# Sheet_UL.net
KiCad netlist of a schematic drawn in Altium Designer
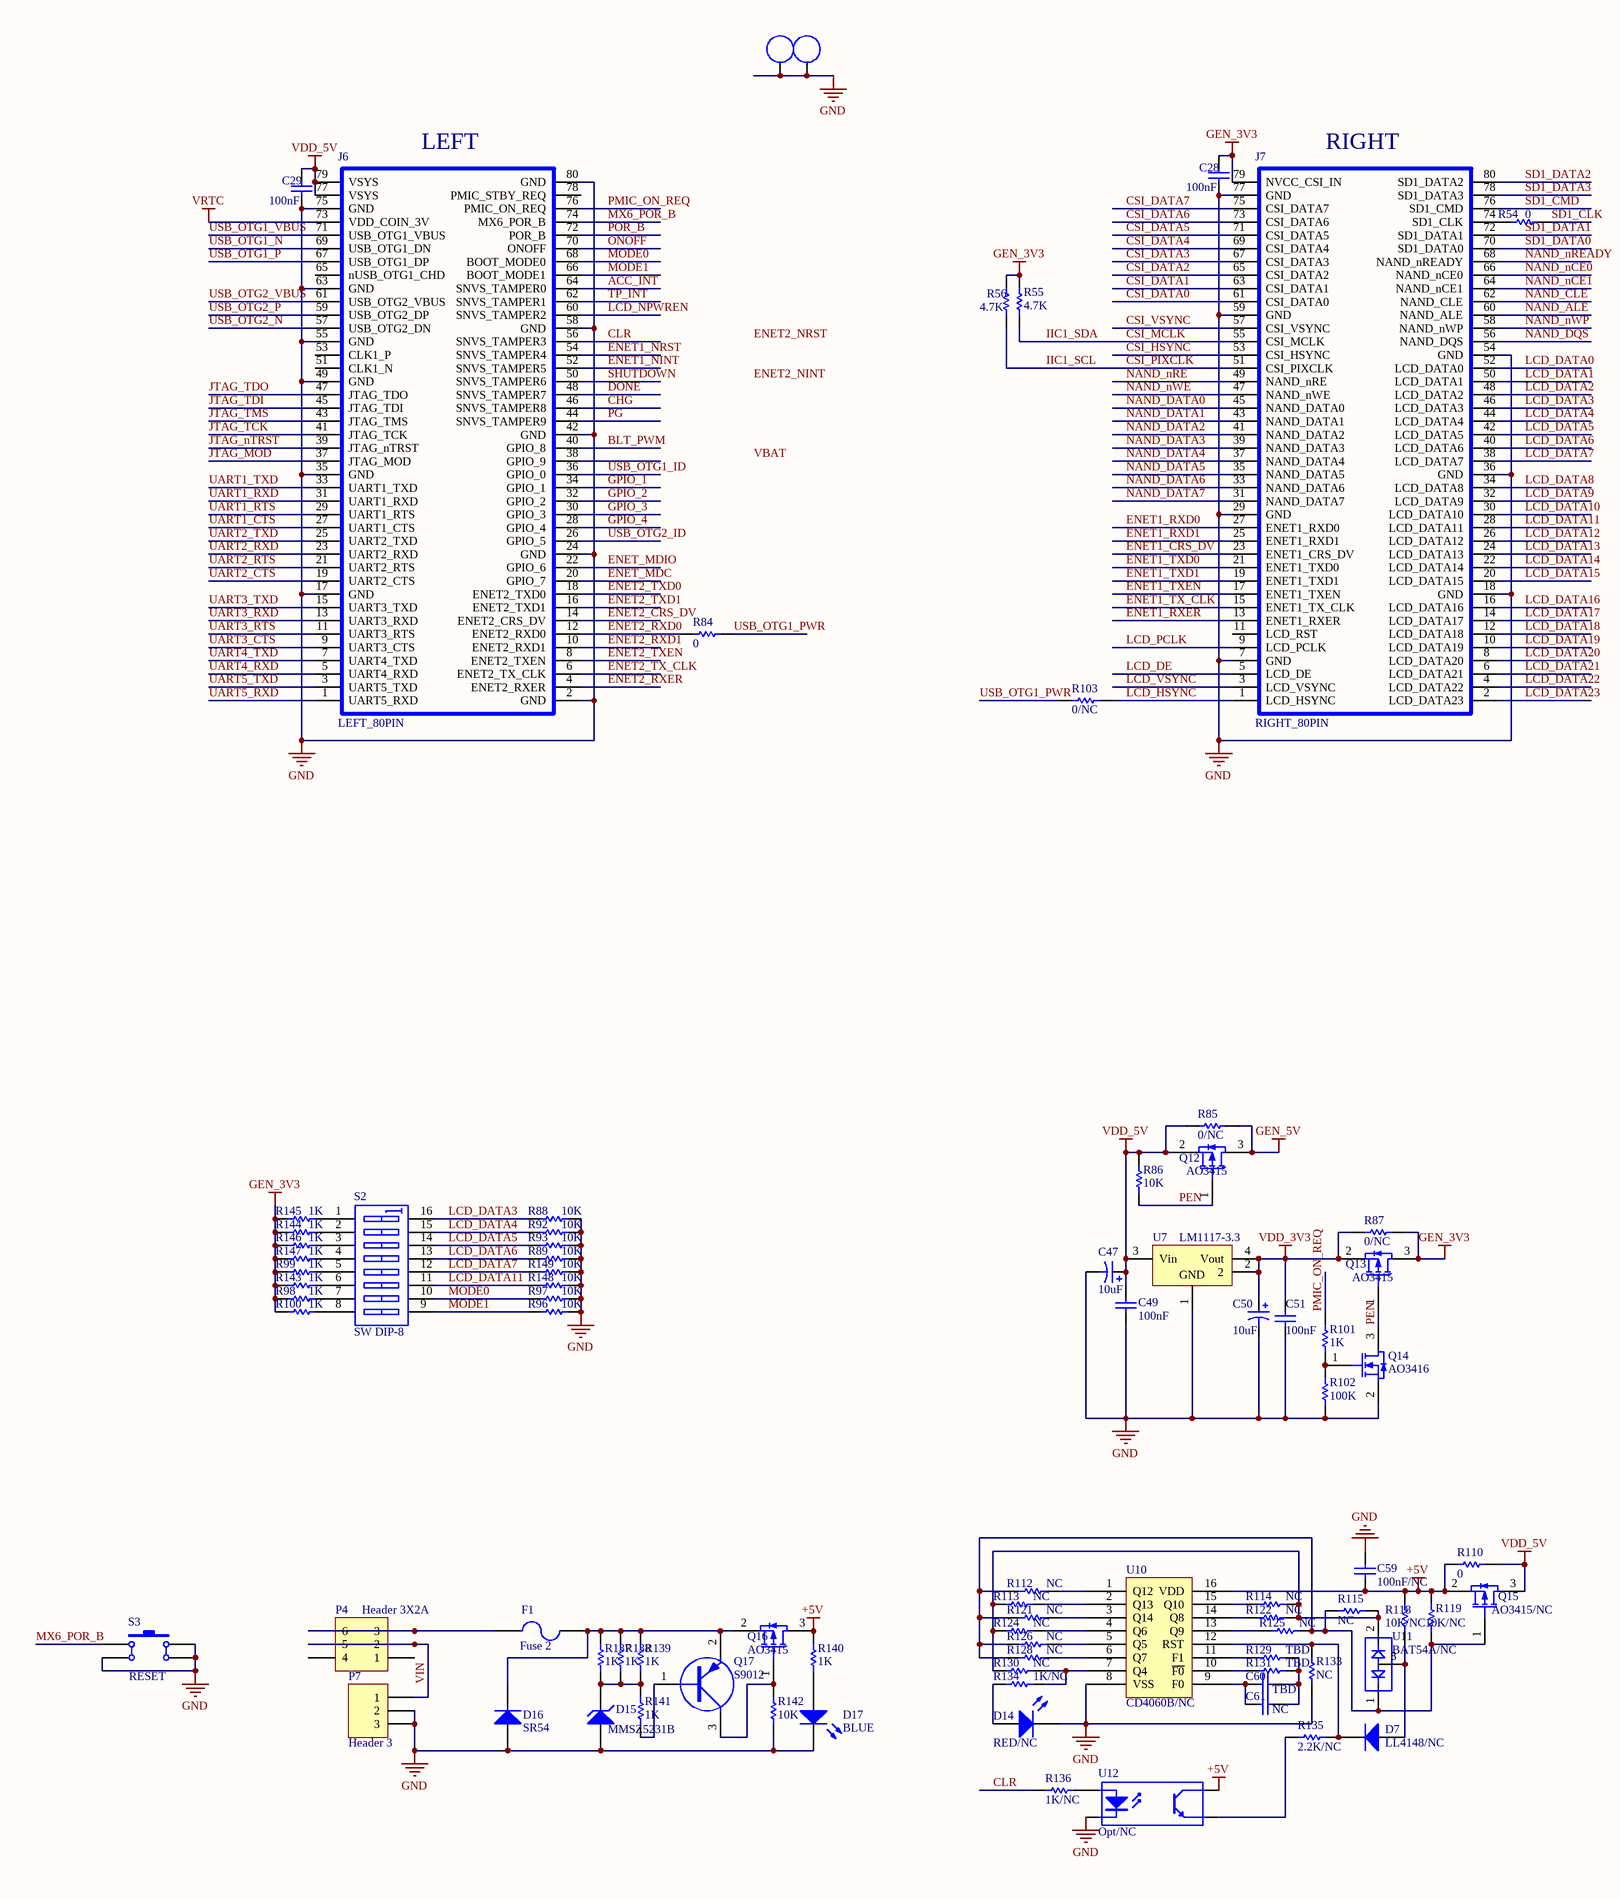
[diagram p0: Sheet_UL.SchDoc, left]
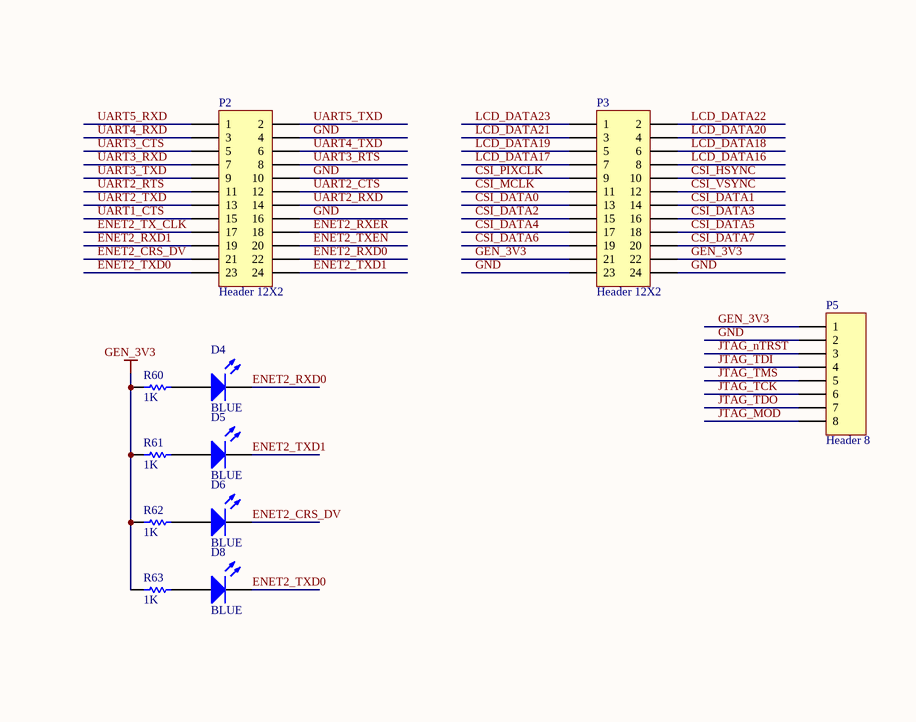
[diagram p1: Sheet_UL.SchDoc, right]

(export (version "E")
  (design (tool "Eeschema 10.0.6"))
  (components
    (comp (ref "C28")
      (value "100nF")
      (footprint "0603")
      (description "Capacitor")
      (fields (field (name "Comment") "Cap") (field (name "PUBLISHER") "Altium Limited"))
      (libsource (lib "Miscellaneous Devices") (part "Cap"))
    )
    (comp (ref "C29")
      (value "100nF")
      (footprint "0603")
      (description "Capacitor")
      (fields (field (name "Comment") "Cap") (field (name "PUBLISHER") "Altium Limited"))
      (libsource (lib "Miscellaneous Devices") (part "Cap"))
    )
    (comp (ref "C47")
      (value "10uF")
      (footprint "3216A")
      (description "Polarized Capacitor (Radial)")
      (fields (field (name "Comment") "Cap Pol1") (field (name "PUBLISHER") "Altium Limited"))
      (libsource (lib "Miscellaneous Devices") (part "Cap Pol1"))
    )
    (comp (ref "C49")
      (value "100nF")
      (footprint "0603")
      (description "Capacitor")
      (fields (field (name "Comment") "Cap") (field (name "PUBLISHER") "Altium Limited"))
      (libsource (lib "Miscellaneous Devices") (part "Cap"))
    )
    (comp (ref "C50")
      (value "10uF")
      (footprint "3216A")
      (description "Polarized Capacitor (Radial)")
      (fields (field (name "Comment") "Cap Pol1") (field (name "PUBLISHER") "Altium Limited"))
      (libsource (lib "Miscellaneous Devices") (part "Cap Pol1"))
    )
    (comp (ref "C51")
      (value "100nF")
      (footprint "0603")
      (description "Capacitor")
      (fields (field (name "Comment") "Cap") (field (name "PUBLISHER") "Altium Limited"))
      (libsource (lib "Miscellaneous Devices") (part "Cap"))
    )
    (comp (ref "C59")
      (value "100nF/NC")
      (footprint "0603")
      (description "Capacitor")
      (fields (field (name "Comment") "Cap") (field (name "PUBLISHER") "Altium Limited"))
      (libsource (lib "Miscellaneous Devices") (part "Cap"))
    )
    (comp (ref "C60")
      (value "TBD")
      (footprint "0603")
      (description "Capacitor")
      (fields (field (name "Comment") "Cap") (field (name "PUBLISHER") "Altium Limited"))
      (libsource (lib "Miscellaneous Devices") (part "Cap"))
    )
    (comp (ref "C61")
      (value "NC")
      (footprint "0603")
      (description "Capacitor")
      (fields (field (name "Comment") "Cap") (field (name "PUBLISHER") "Altium Limited"))
      (libsource (lib "Miscellaneous Devices") (part "Cap"))
    )
    (comp (ref "D4")
      (value "BLUE")
      (footprint "0603_")
      (description "Typical INFRARED GaAs LED")
      (fields (field (name "PUBLISHER") "Altium Limited"))
      (libsource (lib "Miscellaneous Devices") (part "LED0"))
    )
    (comp (ref "D5")
      (value "BLUE")
      (footprint "0603_")
      (description "Typical INFRARED GaAs LED")
      (fields (field (name "PUBLISHER") "Altium Limited"))
      (libsource (lib "Miscellaneous Devices") (part "LED0"))
    )
    (comp (ref "D6")
      (value "BLUE")
      (footprint "0603_")
      (description "Typical INFRARED GaAs LED")
      (fields (field (name "PUBLISHER") "Altium Limited"))
      (libsource (lib "Miscellaneous Devices") (part "LED0"))
    )
    (comp (ref "D7")
      (value "LL4148/NC")
      (footprint "1206_")
      (description "Default Diode")
      (fields (field (name "PUBLISHER") "Altium Limited"))
      (libsource (lib "Miscellaneous Devices") (part "Diode"))
    )
    (comp (ref "D8")
      (value "BLUE")
      (footprint "0603_")
      (description "Typical INFRARED GaAs LED")
      (fields (field (name "PUBLISHER") "Altium Limited"))
      (libsource (lib "Miscellaneous Devices") (part "LED0"))
    )
    (comp (ref "D14")
      (value "RED/NC")
      (footprint "0603_")
      (description "Typical INFRARED GaAs LED")
      (fields (field (name "PUBLISHER") "Altium Limited"))
      (libsource (lib "Miscellaneous Devices") (part "LED0"))
    )
    (comp (ref "D15")
      (value "MMSZ5231B")
      (footprint "SOD-123")
      (description "Zener Diode")
      (fields (field (name "PUBLISHER") "Altium Limited"))
      (libsource (lib "Miscellaneous Devices") (part "D Zener"))
    )
    (comp (ref "D16")
      (value "SR54")
      (footprint "SMB/DO-214AA")
      (description "Default Diode")
      (fields (field (name "PUBLISHER") "Altium Limited"))
      (libsource (lib "Miscellaneous Devices") (part "Diode"))
    )
    (comp (ref "D17")
      (value "BLUE")
      (footprint "0603_")
      (description "Typical INFRARED GaAs LED")
      (fields (field (name "PUBLISHER") "Altium Limited"))
      (libsource (lib "Miscellaneous Devices") (part "LED0"))
    )
    (comp (ref "F1")
      (value "Fuse 2")
      (footprint "1812")
      (description "Fuse")
      (fields (field (name "PUBLISHER") "Altium Limited"))
      (libsource (lib "Miscellaneous Devices") (part "Fuse 2"))
    )
    (comp (ref "H10") (value "hole") (footprint "HOLE_2") (libsource (lib "arm_SL") (part "hole")))
    (comp (ref "H11") (value "hole") (footprint "HOLE_2") (libsource (lib "arm_SL") (part "hole")))
    (comp (ref "J6")
      (value "LEFT_80PIN")
      (footprint "CON_80")
      (libsource (lib "Schlib_UL") (part "LEFT_80PIN"))
    )
    (comp (ref "J7")
      (value "RIGHT_80PIN")
      (footprint "CON_80")
      (libsource (lib "Schlib_UL") (part "RIGHT_80PIN"))
    )
    (comp (ref "P2")
      (value "Header 12X2")
      (footprint "HDR2X12")
      (description "Header, 12-Pin, Dual row")
      (fields (field (name "PUBLISHER") "Altium Limited"))
      (libsource (lib "Miscellaneous Connectors") (part "Header 12X2"))
    )
    (comp (ref "P3")
      (value "Header 12X2")
      (footprint "HDR2X12")
      (description "Header, 12-Pin, Dual row")
      (fields (field (name "PUBLISHER") "Altium Limited"))
      (libsource (lib "Miscellaneous Connectors") (part "Header 12X2"))
    )
    (comp (ref "P4")
      (value "Header 3X2A")
      (footprint "ZSKG_8.5_8.5")
      (description "Header, 3-Pin, Dual row")
      (fields (field (name "PUBLISHER") "Altium Limited"))
      (libsource (lib "Miscellaneous Connectors") (part "Header 3X2A"))
    )
    (comp (ref "P5")
      (value "Header 8")
      (footprint "HDR1X8")
      (description "Header, 8-Pin")
      (fields (field (name "PUBLISHER") "Altium Limited"))
      (libsource (lib "Miscellaneous Connectors") (part "Header 8"))
    )
    (comp (ref "P7")
      (value "Header 3")
      (footprint "JACK-2.5MM_B")
      (description "Header, 3-Pin")
      (fields (field (name "PUBLISHER") "Altium Limited"))
      (libsource (lib "Miscellaneous Connectors") (part "Header 3"))
    )
    (comp (ref "Q12")
      (value "AO3415")
      (footprint "SOT23")
      (description "P-Channel MOSFET")
      (fields (field (name "PUBLISHER") "Altium Limited"))
      (libsource (lib "Schlib1") (part "MOSFET-P_1"))
    )
    (comp (ref "Q13")
      (value "AO3415")
      (footprint "SOT23")
      (description "P-Channel MOSFET")
      (fields (field (name "PUBLISHER") "Altium Limited"))
      (libsource (lib "Schlib1") (part "MOSFET-P_1"))
    )
    (comp (ref "Q14")
      (value "AO3416")
      (footprint "SOT23")
      (description "N-Channel MOSFET")
      (fields (field (name "PUBLISHER") "Altium Limited"))
      (libsource (lib "Schlib_UL") (part "MOSFET-P_1"))
    )
    (comp (ref "Q15")
      (value "AO3415/NC")
      (footprint "SOT23")
      (description "P-Channel MOSFET")
      (fields (field (name "PUBLISHER") "Altium Limited"))
      (libsource (lib "Schlib1") (part "MOSFET-P_1"))
    )
    (comp (ref "Q16")
      (value "AO3415")
      (footprint "SOT23")
      (description "P-Channel MOSFET")
      (fields (field (name "PUBLISHER") "Altium Limited"))
      (libsource (lib "Schlib1") (part "MOSFET-P_1"))
    )
    (comp (ref "Q17")
      (value "S9012")
      (footprint "SOT23")
      (description "PNP Transistor")
      (libsource (lib "Schlib_YX") (part "PNP"))
    )
    (comp (ref "R54")
      (value "0")
      (footprint "0603")
      (description "Resistor")
      (fields (field (name "Comment") "Res1") (field (name "PUBLISHER") "Altium Limited"))
      (libsource (lib "Miscellaneous Devices") (part "Res1"))
    )
    (comp (ref "R55")
      (value "4.7K")
      (footprint "0603")
      (description "Resistor")
      (fields (field (name "Comment") "Res1") (field (name "PUBLISHER") "Altium Limited"))
      (libsource (lib "Miscellaneous Devices") (part "Res1"))
    )
    (comp (ref "R56")
      (value "4.7K")
      (footprint "0603")
      (description "Resistor")
      (fields (field (name "Comment") "Res1") (field (name "PUBLISHER") "Altium Limited"))
      (libsource (lib "Miscellaneous Devices") (part "Res1"))
    )
    (comp (ref "R60")
      (value "1K")
      (footprint "0603")
      (description "Resistor")
      (fields (field (name "Comment") "Res1") (field (name "PUBLISHER") "Altium Limited"))
      (libsource (lib "Miscellaneous Devices") (part "Res1"))
    )
    (comp (ref "R61")
      (value "1K")
      (footprint "0603")
      (description "Resistor")
      (fields (field (name "Comment") "Res1") (field (name "PUBLISHER") "Altium Limited"))
      (libsource (lib "Miscellaneous Devices") (part "Res1"))
    )
    (comp (ref "R62")
      (value "1K")
      (footprint "0603")
      (description "Resistor")
      (fields (field (name "Comment") "Res1") (field (name "PUBLISHER") "Altium Limited"))
      (libsource (lib "Miscellaneous Devices") (part "Res1"))
    )
    (comp (ref "R63")
      (value "1K")
      (footprint "0603")
      (description "Resistor")
      (fields (field (name "Comment") "Res1") (field (name "PUBLISHER") "Altium Limited"))
      (libsource (lib "Miscellaneous Devices") (part "Res1"))
    )
    (comp (ref "R84")
      (value "0")
      (footprint "0603")
      (description "Resistor")
      (fields (field (name "Comment") "Res1") (field (name "PUBLISHER") "Altium Limited"))
      (libsource (lib "Miscellaneous Devices") (part "Res1"))
    )
    (comp (ref "R85")
      (value "0/NC")
      (footprint "0805")
      (description "Resistor")
      (fields (field (name "Comment") "Res1") (field (name "PUBLISHER") "Altium Limited"))
      (libsource (lib "Miscellaneous Devices") (part "Res1"))
    )
    (comp (ref "R86")
      (value "10K")
      (footprint "0603")
      (description "Resistor")
      (fields (field (name "Comment") "Res1") (field (name "PUBLISHER") "Altium Limited"))
      (libsource (lib "Miscellaneous Devices") (part "Res1"))
    )
    (comp (ref "R87")
      (value "0/NC")
      (footprint "0603")
      (description "Resistor")
      (fields (field (name "Comment") "Res1") (field (name "PUBLISHER") "Altium Limited"))
      (libsource (lib "Miscellaneous Devices") (part "Res1"))
    )
    (comp (ref "R88")
      (value "10K")
      (footprint "0603")
      (description "Resistor")
      (fields (field (name "Comment") "Res1") (field (name "PUBLISHER") "Altium Limited"))
      (libsource (lib "Miscellaneous Devices") (part "Res1"))
    )
    (comp (ref "R89")
      (value "10K")
      (footprint "0603")
      (description "Resistor")
      (fields (field (name "Comment") "Res1") (field (name "PUBLISHER") "Altium Limited"))
      (libsource (lib "Miscellaneous Devices") (part "Res1"))
    )
    (comp (ref "R92")
      (value "10K")
      (footprint "0603")
      (description "Resistor")
      (fields (field (name "Comment") "Res1") (field (name "PUBLISHER") "Altium Limited"))
      (libsource (lib "Miscellaneous Devices") (part "Res1"))
    )
    (comp (ref "R93")
      (value "10K")
      (footprint "0603")
      (description "Resistor")
      (fields (field (name "Comment") "Res1") (field (name "PUBLISHER") "Altium Limited"))
      (libsource (lib "Miscellaneous Devices") (part "Res1"))
    )
    (comp (ref "R96")
      (value "10K")
      (footprint "0603")
      (description "Resistor")
      (fields (field (name "Comment") "Res1") (field (name "PUBLISHER") "Altium Limited"))
      (libsource (lib "Miscellaneous Devices") (part "Res1"))
    )
    (comp (ref "R97")
      (value "10K")
      (footprint "0603")
      (description "Resistor")
      (fields (field (name "Comment") "Res1") (field (name "PUBLISHER") "Altium Limited"))
      (libsource (lib "Miscellaneous Devices") (part "Res1"))
    )
    (comp (ref "R98")
      (value "1K")
      (footprint "0603")
      (description "Resistor")
      (fields (field (name "Comment") "Res1") (field (name "PUBLISHER") "Altium Limited"))
      (libsource (lib "Miscellaneous Devices") (part "Res1"))
    )
    (comp (ref "R99")
      (value "1K")
      (footprint "0603")
      (description "Resistor")
      (fields (field (name "Comment") "Res1") (field (name "PUBLISHER") "Altium Limited"))
      (libsource (lib "Miscellaneous Devices") (part "Res1"))
    )
    (comp (ref "R100")
      (value "1K")
      (footprint "0603")
      (description "Resistor")
      (fields (field (name "Comment") "Res1") (field (name "PUBLISHER") "Altium Limited"))
      (libsource (lib "Miscellaneous Devices") (part "Res1"))
    )
    (comp (ref "R101")
      (value "1K")
      (footprint "0603")
      (description "Resistor")
      (fields (field (name "Comment") "Res1") (field (name "PUBLISHER") "Altium Limited"))
      (libsource (lib "Miscellaneous Devices") (part "Res1"))
    )
    (comp (ref "R102")
      (value "100K")
      (footprint "0603")
      (description "Resistor")
      (fields (field (name "Comment") "Res1") (field (name "PUBLISHER") "Altium Limited"))
      (libsource (lib "Miscellaneous Devices") (part "Res1"))
    )
    (comp (ref "R103")
      (value "0/NC")
      (footprint "0603")
      (description "Resistor")
      (fields (field (name "Comment") "Res1") (field (name "PUBLISHER") "Altium Limited"))
      (libsource (lib "Miscellaneous Devices") (part "Res1"))
    )
    (comp (ref "R110")
      (value "0")
      (footprint "0805")
      (description "Resistor")
      (fields (field (name "Comment") "Res1") (field (name "PUBLISHER") "Altium Limited"))
      (libsource (lib "Miscellaneous Devices") (part "Res1"))
    )
    (comp (ref "R112")
      (value "NC")
      (footprint "0603")
      (description "Resistor")
      (fields (field (name "Comment") "Res1") (field (name "PUBLISHER") "Altium Limited"))
      (libsource (lib "Miscellaneous Devices") (part "Res1"))
    )
    (comp (ref "R113")
      (value "NC")
      (footprint "0603")
      (description "Resistor")
      (fields (field (name "Comment") "Res1") (field (name "PUBLISHER") "Altium Limited"))
      (libsource (lib "Miscellaneous Devices") (part "Res1"))
    )
    (comp (ref "R114")
      (value "NC")
      (footprint "0603")
      (description "Resistor")
      (fields (field (name "Comment") "Res1") (field (name "PUBLISHER") "Altium Limited"))
      (libsource (lib "Miscellaneous Devices") (part "Res1"))
    )
    (comp (ref "R115")
      (value "NC")
      (footprint "0603")
      (description "Resistor")
      (fields (field (name "Comment") "Res1") (field (name "PUBLISHER") "Altium Limited"))
      (libsource (lib "Miscellaneous Devices") (part "Res1"))
    )
    (comp (ref "R118")
      (value "10K/NC")
      (footprint "0603")
      (description "Resistor")
      (fields (field (name "Comment") "Res1") (field (name "PUBLISHER") "Altium Limited"))
      (libsource (lib "Miscellaneous Devices") (part "Res1"))
    )
    (comp (ref "R119")
      (value "10K/NC")
      (footprint "0603")
      (description "Resistor")
      (fields (field (name "Comment") "Res1") (field (name "PUBLISHER") "Altium Limited"))
      (libsource (lib "Miscellaneous Devices") (part "Res1"))
    )
    (comp (ref "R121")
      (value "NC")
      (footprint "0603")
      (description "Resistor")
      (fields (field (name "Comment") "Res1") (field (name "PUBLISHER") "Altium Limited"))
      (libsource (lib "Miscellaneous Devices") (part "Res1"))
    )
    (comp (ref "R122")
      (value "NC")
      (footprint "0603")
      (description "Resistor")
      (fields (field (name "Comment") "Res1") (field (name "PUBLISHER") "Altium Limited"))
      (libsource (lib "Miscellaneous Devices") (part "Res1"))
    )
    (comp (ref "R124")
      (value "NC")
      (footprint "0603")
      (description "Resistor")
      (fields (field (name "Comment") "Res1") (field (name "PUBLISHER") "Altium Limited"))
      (libsource (lib "Miscellaneous Devices") (part "Res1"))
    )
    (comp (ref "R125")
      (value "NC")
      (footprint "0603")
      (description "Resistor")
      (fields (field (name "Comment") "Res1") (field (name "PUBLISHER") "Altium Limited"))
      (libsource (lib "Miscellaneous Devices") (part "Res1"))
    )
    (comp (ref "R126")
      (value "NC")
      (footprint "0603")
      (description "Resistor")
      (fields (field (name "Comment") "Res1") (field (name "PUBLISHER") "Altium Limited"))
      (libsource (lib "Miscellaneous Devices") (part "Res1"))
    )
    (comp (ref "R128")
      (value "NC")
      (footprint "0603")
      (description "Resistor")
      (fields (field (name "Comment") "Res1") (field (name "PUBLISHER") "Altium Limited"))
      (libsource (lib "Miscellaneous Devices") (part "Res1"))
    )
    (comp (ref "R129")
      (value "TBD")
      (footprint "0603")
      (description "Resistor")
      (fields (field (name "Comment") "Res1") (field (name "PUBLISHER") "Altium Limited"))
      (libsource (lib "Miscellaneous Devices") (part "Res1"))
    )
    (comp (ref "R130")
      (value "NC")
      (footprint "0603")
      (description "Resistor")
      (fields (field (name "Comment") "Res1") (field (name "PUBLISHER") "Altium Limited"))
      (libsource (lib "Miscellaneous Devices") (part "Res1"))
    )
    (comp (ref "R131")
      (value "TBD")
      (footprint "0603")
      (description "Resistor")
      (fields (field (name "Comment") "Res1") (field (name "PUBLISHER") "Altium Limited"))
      (libsource (lib "Miscellaneous Devices") (part "Res1"))
    )
    (comp (ref "R133")
      (value "NC")
      (footprint "0603")
      (description "Resistor")
      (fields (field (name "Comment") "Res1") (field (name "PUBLISHER") "Altium Limited"))
      (libsource (lib "Miscellaneous Devices") (part "Res1"))
    )
    (comp (ref "R134")
      (value "1K/NC")
      (footprint "0603")
      (description "Resistor")
      (fields (field (name "Comment") "Res1") (field (name "PUBLISHER") "Altium Limited"))
      (libsource (lib "Miscellaneous Devices") (part "Res1"))
    )
    (comp (ref "R135")
      (value "2.2K/NC")
      (footprint "0603")
      (description "Resistor")
      (fields (field (name "Comment") "Res1") (field (name "PUBLISHER") "Altium Limited"))
      (libsource (lib "Miscellaneous Devices") (part "Res1"))
    )
    (comp (ref "R136")
      (value "1K/NC")
      (footprint "0603")
      (description "Resistor")
      (fields (field (name "Comment") "Res1") (field (name "PUBLISHER") "Altium Limited"))
      (libsource (lib "Miscellaneous Devices") (part "Res1"))
    )
    (comp (ref "R137")
      (value "1K")
      (footprint "0603")
      (description "Resistor")
      (fields (field (name "Comment") "Res1") (field (name "PUBLISHER") "Altium Limited"))
      (libsource (lib "Miscellaneous Devices") (part "Res1"))
    )
    (comp (ref "R138")
      (value "1K")
      (footprint "0603")
      (description "Resistor")
      (fields (field (name "Comment") "Res1") (field (name "PUBLISHER") "Altium Limited"))
      (libsource (lib "Miscellaneous Devices") (part "Res1"))
    )
    (comp (ref "R139")
      (value "1K")
      (footprint "0603")
      (description "Resistor")
      (fields (field (name "Comment") "Res1") (field (name "PUBLISHER") "Altium Limited"))
      (libsource (lib "Miscellaneous Devices") (part "Res1"))
    )
    (comp (ref "R140")
      (value "1K")
      (footprint "0603")
      (description "Resistor")
      (fields (field (name "Comment") "Res1") (field (name "PUBLISHER") "Altium Limited"))
      (libsource (lib "Miscellaneous Devices") (part "Res1"))
    )
    (comp (ref "R141")
      (value "1K")
      (footprint "0603")
      (description "Resistor")
      (fields (field (name "Comment") "Res1") (field (name "PUBLISHER") "Altium Limited"))
      (libsource (lib "Miscellaneous Devices") (part "Res1"))
    )
    (comp (ref "R142")
      (value "10K")
      (footprint "0603")
      (description "Resistor")
      (fields (field (name "Comment") "Res1") (field (name "PUBLISHER") "Altium Limited"))
      (libsource (lib "Miscellaneous Devices") (part "Res1"))
    )
    (comp (ref "R143")
      (value "1K")
      (footprint "0603")
      (description "Resistor")
      (fields (field (name "Comment") "Res1") (field (name "PUBLISHER") "Altium Limited"))
      (libsource (lib "Miscellaneous Devices") (part "Res1"))
    )
    (comp (ref "R144")
      (value "1K")
      (footprint "0603")
      (description "Resistor")
      (fields (field (name "Comment") "Res1") (field (name "PUBLISHER") "Altium Limited"))
      (libsource (lib "Miscellaneous Devices") (part "Res1"))
    )
    (comp (ref "R145")
      (value "1K")
      (footprint "0603")
      (description "Resistor")
      (fields (field (name "Comment") "Res1") (field (name "PUBLISHER") "Altium Limited"))
      (libsource (lib "Miscellaneous Devices") (part "Res1"))
    )
    (comp (ref "R146")
      (value "1K")
      (footprint "0603")
      (description "Resistor")
      (fields (field (name "Comment") "Res1") (field (name "PUBLISHER") "Altium Limited"))
      (libsource (lib "Miscellaneous Devices") (part "Res1"))
    )
    (comp (ref "R147")
      (value "1K")
      (footprint "0603")
      (description "Resistor")
      (fields (field (name "Comment") "Res1") (field (name "PUBLISHER") "Altium Limited"))
      (libsource (lib "Miscellaneous Devices") (part "Res1"))
    )
    (comp (ref "R148")
      (value "10K")
      (footprint "0603")
      (description "Resistor")
      (fields (field (name "Comment") "Res1") (field (name "PUBLISHER") "Altium Limited"))
      (libsource (lib "Miscellaneous Devices") (part "Res1"))
    )
    (comp (ref "R149")
      (value "10K")
      (footprint "0603")
      (description "Resistor")
      (fields (field (name "Comment") "Res1") (field (name "PUBLISHER") "Altium Limited"))
      (libsource (lib "Miscellaneous Devices") (part "Res1"))
    )
    (comp (ref "S2")
      (value "SW DIP-8")
      (footprint "SMD_8")
      (description "DIP Switch, 8 Position, SPST")
      (fields (field (name "PUBLISHER") "Altium Limited"))
      (libsource (lib "Miscellaneous Devices") (part "SW DIP-8"))
    )
    (comp (ref "S3")
      (value "RESET")
      (footprint "SW_6-6")
      (fields (field (name "PUBLISHER") "Altium Limited"))
      (libsource (lib "MySchlib") (part "SW-PB-4"))
    )
    (comp (ref "U7")
      (value "LM1117-3.3")
      (footprint "SOT-223")
      (description "Voltage Regulator")
      (fields (field (name "PUBLISHER") "Altium Limited"))
      (libsource (lib "arm_SL") (part "Volt Reg"))
    )
    (comp (ref "U10") (value "CD4060B/NC") (footprint "SO-16") (libsource (lib "Schlib_UL") (part "CD4060B")))
    (comp (ref "U11") (value "BAT54A/NC") (footprint "SOT23") (libsource (lib "Schlib_UL") (part "BAT54A")))
    (comp (ref "U12")
      (value "Opt/NC")
      (footprint "SO-4")
      (description "4-Pin Phototransistor Optocoupler")
      (fields (field (name "PUBLISHER") "Altium Limited"))
      (libsource (lib "Miscellaneous Devices") (part "Optoisolator1"))
    )
  )
  (nets
    (net (code "1") (name "+5V") (class "Default")
      (node (ref "C59") (pin "2") (pinfunction "2_2") (pintype "passive"))
      (node (ref "Q15") (pin "2") (pinfunction "S_2") (pintype "passive"))
      (node (ref "Q16") (pin "3") (pinfunction "D_3") (pintype "passive"))
      (node (ref "R110") (pin "2") (pinfunction "2_2") (pintype "passive"))
      (node (ref "R118") (pin "2") (pinfunction "2_2") (pintype "passive"))
      (node (ref "R119") (pin "2") (pinfunction "2_2") (pintype "passive"))
      (node (ref "R140") (pin "2") (pinfunction "2_2") (pintype "passive"))
      (node (ref "U10") (pin "16") (pinfunction "VDD_16") (pintype "passive"))
      (node (ref "U12") (pin "4") (pinfunction "C_4") (pintype "passive"))
    )
    (net (code "2") (name "/ACC_INT") (class "Default")
      (node (ref "J6") (pin "64") (pinfunction "SNVS_TAMPER0_64") (pintype "passive"))
    )
    (net (code "3") (name "/BLT_PWM") (class "Default")
      (node (ref "J6") (pin "40") (pinfunction "GPIO_8_40") (pintype "passive"))
    )
    (net (code "4") (name "/CHG") (class "Default")
      (node (ref "J6") (pin "46") (pinfunction "SNVS_TAMPER8_46") (pintype "passive"))
    )
    (net (code "5") (name "/CLR") (class "Default")
      (node (ref "J6") (pin "56") (pinfunction "SNVS_TAMPER3_56") (pintype "passive"))
      (node (ref "R136") (pin "1") (pinfunction "1_1") (pintype "passive"))
    )
    (net (code "6") (name "/CSI_DATA0") (class "Default")
      (node (ref "J7") (pin "61") (pinfunction "CSI_DATA0_61") (pintype "passive"))
      (node (ref "P3") (pin "13") (pinfunction "13_13") (pintype "passive"))
    )
    (net (code "7") (name "/CSI_DATA1") (class "Default")
      (node (ref "J7") (pin "63") (pinfunction "CSI_DATA1_63") (pintype "passive"))
      (node (ref "P3") (pin "14") (pinfunction "14_14") (pintype "passive"))
    )
    (net (code "8") (name "/CSI_DATA2") (class "Default")
      (node (ref "J7") (pin "65") (pinfunction "CSI_DATA2_65") (pintype "passive"))
      (node (ref "P3") (pin "15") (pinfunction "15_15") (pintype "passive"))
    )
    (net (code "9") (name "/CSI_DATA3") (class "Default")
      (node (ref "J7") (pin "67") (pinfunction "CSI_DATA3_67") (pintype "passive"))
      (node (ref "P3") (pin "16") (pinfunction "16_16") (pintype "passive"))
    )
    (net (code "10") (name "/CSI_DATA4") (class "Default")
      (node (ref "J7") (pin "69") (pinfunction "CSI_DATA4_69") (pintype "passive"))
      (node (ref "P3") (pin "17") (pinfunction "17_17") (pintype "passive"))
    )
    (net (code "11") (name "/CSI_DATA5") (class "Default")
      (node (ref "J7") (pin "71") (pinfunction "CSI_DATA5_71") (pintype "passive"))
      (node (ref "P3") (pin "18") (pinfunction "18_18") (pintype "passive"))
    )
    (net (code "12") (name "/CSI_DATA6") (class "Default")
      (node (ref "J7") (pin "73") (pinfunction "CSI_DATA6_73") (pintype "passive"))
      (node (ref "P3") (pin "19") (pinfunction "19_19") (pintype "passive"))
    )
    (net (code "13") (name "/CSI_DATA7") (class "Default")
      (node (ref "J7") (pin "75") (pinfunction "CSI_DATA7_75") (pintype "passive"))
      (node (ref "P3") (pin "20") (pinfunction "20_20") (pintype "passive"))
    )
    (net (code "14") (name "/CSI_HSYNC") (class "Default")
      (node (ref "J7") (pin "53") (pinfunction "CSI_HSYNC_53") (pintype "passive"))
      (node (ref "P3") (pin "10") (pinfunction "10_10") (pintype "passive"))
    )
    (net (code "15") (name "/CSI_MCLK") (class "Default")
      (node (ref "J7") (pin "55") (pinfunction "CSI_MCLK_55") (pintype "passive"))
      (node (ref "P3") (pin "11") (pinfunction "11_11") (pintype "passive"))
      (node (ref "R55") (pin "1") (pinfunction "1_1") (pintype "passive"))
    )
    (net (code "16") (name "/CSI_PIXCLK") (class "Default")
      (node (ref "J7") (pin "51") (pinfunction "CSI_PIXCLK_51") (pintype "passive"))
      (node (ref "P3") (pin "9") (pinfunction "9_9") (pintype "passive"))
      (node (ref "R56") (pin "1") (pinfunction "1_1") (pintype "passive"))
    )
    (net (code "17") (name "/CSI_VSYNC") (class "Default")
      (node (ref "J7") (pin "57") (pinfunction "CSI_VSYNC_57") (pintype "passive"))
      (node (ref "P3") (pin "12") (pinfunction "12_12") (pintype "passive"))
    )
    (net (code "18") (name "/DONE") (class "Default")
      (node (ref "J6") (pin "48") (pinfunction "SNVS_TAMPER7_48") (pintype "passive"))
    )
    (net (code "19") (name "/ENET1_CRS_DV") (class "Default")
      (node (ref "J7") (pin "23") (pinfunction "ENET1_CRS_DV_23") (pintype "passive"))
    )
    (net (code "20") (name "/ENET1_NINT") (class "Default")
      (node (ref "J6") (pin "52") (pinfunction "SNVS_TAMPER5_52") (pintype "passive"))
    )
    (net (code "21") (name "/ENET1_NRST") (class "Default")
      (node (ref "J6") (pin "54") (pinfunction "SNVS_TAMPER4_54") (pintype "passive"))
    )
    (net (code "22") (name "/ENET1_RXD0") (class "Default")
      (node (ref "J7") (pin "27") (pinfunction "ENET1_RXD0_27") (pintype "passive"))
    )
    (net (code "23") (name "/ENET1_RXD1") (class "Default")
      (node (ref "J7") (pin "25") (pinfunction "ENET1_RXD1_25") (pintype "passive"))
    )
    (net (code "24") (name "/ENET1_RXER") (class "Default")
      (node (ref "J7") (pin "13") (pinfunction "ENET1_RXER_13") (pintype "passive"))
    )
    (net (code "25") (name "/ENET1_TXD0") (class "Default")
      (node (ref "J7") (pin "21") (pinfunction "ENET1_TXD0_21") (pintype "passive"))
    )
    (net (code "26") (name "/ENET1_TXD1") (class "Default")
      (node (ref "J7") (pin "19") (pinfunction "ENET1_TXD1_19") (pintype "passive"))
    )
    (net (code "27") (name "/ENET1_TXEN") (class "Default")
      (node (ref "J7") (pin "17") (pinfunction "ENET1_TXEN_17") (pintype "passive"))
    )
    (net (code "28") (name "/ENET1_TX_CLK") (class "Default")
      (node (ref "J7") (pin "15") (pinfunction "ENET1_TX_CLK_15") (pintype "passive"))
    )
    (net (code "29") (name "/ENET2_CRS_DV") (class "Default")
      (node (ref "D6") (pin "2") (pinfunction "K_2") (pintype "passive"))
      (node (ref "J6") (pin "14") (pinfunction "ENET2_CRS_DV_14") (pintype "passive"))
      (node (ref "P2") (pin "21") (pinfunction "21_21") (pintype "passive"))
    )
    (net (code "32") (name "/ENET2_RXD0") (class "Default")
      (node (ref "D4") (pin "2") (pinfunction "K_2") (pintype "passive"))
      (node (ref "J6") (pin "12") (pinfunction "ENET2_RXD0_12") (pintype "passive"))
      (node (ref "P2") (pin "22") (pinfunction "22_22") (pintype "passive"))
      (node (ref "R84") (pin "1") (pinfunction "1_1") (pintype "passive"))
    )
    (net (code "33") (name "/ENET2_RXD1") (class "Default")
      (node (ref "J6") (pin "10") (pinfunction "ENET2_RXD1_10") (pintype "passive"))
      (node (ref "P2") (pin "19") (pinfunction "19_19") (pintype "passive"))
    )
    (net (code "34") (name "/ENET2_RXER") (class "Default")
      (node (ref "J6") (pin "4") (pinfunction "ENET2_RXER_4") (pintype "passive"))
      (node (ref "P2") (pin "18") (pinfunction "18_18") (pintype "passive"))
    )
    (net (code "35") (name "/ENET2_TXD0") (class "Default")
      (node (ref "D8") (pin "2") (pinfunction "K_2") (pintype "passive"))
      (node (ref "J6") (pin "18") (pinfunction "ENET2_TXD0_18") (pintype "passive"))
      (node (ref "P2") (pin "23") (pinfunction "23_23") (pintype "passive"))
    )
    (net (code "36") (name "/ENET2_TXD1") (class "Default")
      (node (ref "D5") (pin "2") (pinfunction "K_2") (pintype "passive"))
      (node (ref "J6") (pin "16") (pinfunction "ENET2_TXD1_16") (pintype "passive"))
      (node (ref "P2") (pin "24") (pinfunction "24_24") (pintype "passive"))
    )
    (net (code "37") (name "/ENET2_TXEN") (class "Default")
      (node (ref "J6") (pin "8") (pinfunction "ENET2_TXEN_8") (pintype "passive"))
      (node (ref "P2") (pin "20") (pinfunction "20_20") (pintype "passive"))
    )
    (net (code "38") (name "/ENET2_TX_CLK") (class "Default")
      (node (ref "J6") (pin "6") (pinfunction "ENET2_TX_CLK_6") (pintype "passive"))
      (node (ref "P2") (pin "17") (pinfunction "17_17") (pintype "passive"))
    )
    (net (code "39") (name "/ENET_MDC") (class "Default")
      (node (ref "J6") (pin "20") (pinfunction "GPIO_7_20") (pintype "passive"))
    )
    (net (code "40") (name "/ENET_MDIO") (class "Default")
      (node (ref "J6") (pin "22") (pinfunction "GPIO_6_22") (pintype "passive"))
    )
    (net (code "41") (name "/GPIO_1") (class "Default")
      (node (ref "J6") (pin "34") (pinfunction "GPIO_1_34") (pintype "passive"))
    )
    (net (code "42") (name "/GPIO_2") (class "Default")
      (node (ref "J6") (pin "32") (pinfunction "GPIO_2_32") (pintype "passive"))
    )
    (net (code "43") (name "/GPIO_3") (class "Default")
      (node (ref "J6") (pin "30") (pinfunction "GPIO_3_30") (pintype "passive"))
    )
    (net (code "44") (name "/GPIO_4") (class "Default")
      (node (ref "J6") (pin "28") (pinfunction "GPIO_4_28") (pintype "passive"))
    )
    (net (code "45") (name "/JTAG_MOD") (class "Default")
      (node (ref "J6") (pin "37") (pinfunction "JTAG_MOD_37") (pintype "passive"))
      (node (ref "P5") (pin "8") (pinfunction "8_8") (pintype "passive"))
    )
    (net (code "46") (name "/JTAG_TCK") (class "Default")
      (node (ref "J6") (pin "41") (pinfunction "JTAG_TCK_41") (pintype "passive"))
      (node (ref "P5") (pin "6") (pinfunction "6_6") (pintype "passive"))
    )
    (net (code "47") (name "/JTAG_TDI") (class "Default")
      (node (ref "J6") (pin "45") (pinfunction "JTAG_TDI_45") (pintype "passive"))
      (node (ref "P5") (pin "4") (pinfunction "4_4") (pintype "passive"))
    )
    (net (code "48") (name "/JTAG_TDO") (class "Default")
      (node (ref "J6") (pin "47") (pinfunction "JTAG_TDO_47") (pintype "passive"))
      (node (ref "P5") (pin "7") (pinfunction "7_7") (pintype "passive"))
    )
    (net (code "49") (name "/JTAG_TMS") (class "Default")
      (node (ref "J6") (pin "43") (pinfunction "JTAG_TMS_43") (pintype "passive"))
      (node (ref "P5") (pin "5") (pinfunction "5_5") (pintype "passive"))
    )
    (net (code "50") (name "/JTAG_nTRST") (class "Default")
      (node (ref "J6") (pin "39") (pinfunction "JTAG_nTRST_39") (pintype "passive"))
      (node (ref "P5") (pin "3") (pinfunction "3_3") (pintype "passive"))
    )
    (net (code "51") (name "/LCD_DATA0") (class "Default")
      (node (ref "J7") (pin "52") (pinfunction "LCD_DATA0_52") (pintype "passive"))
    )
    (net (code "52") (name "/LCD_DATA1") (class "Default")
      (node (ref "J7") (pin "50") (pinfunction "LCD_DATA1_50") (pintype "passive"))
    )
    (net (code "53") (name "/LCD_DATA2") (class "Default")
      (node (ref "J7") (pin "48") (pinfunction "LCD_DATA2_48") (pintype "passive"))
    )
    (net (code "54") (name "/LCD_DATA3") (class "Default")
      (node (ref "J7") (pin "46") (pinfunction "LCD_DATA3_46") (pintype "passive"))
      (node (ref "R88") (pin "1") (pinfunction "1_1") (pintype "passive"))
      (node (ref "S2") (pin "16") (pinfunction "B1_16") (pintype "passive"))
    )
    (net (code "55") (name "/LCD_DATA4") (class "Default")
      (node (ref "J7") (pin "44") (pinfunction "LCD_DATA4_44") (pintype "passive"))
      (node (ref "R92") (pin "1") (pinfunction "1_1") (pintype "passive"))
      (node (ref "S2") (pin "15") (pinfunction "B2_15") (pintype "passive"))
    )
    (net (code "56") (name "/LCD_DATA5") (class "Default")
      (node (ref "J7") (pin "42") (pinfunction "LCD_DATA5_42") (pintype "passive"))
      (node (ref "R93") (pin "1") (pinfunction "1_1") (pintype "passive"))
      (node (ref "S2") (pin "14") (pinfunction "B3_14") (pintype "passive"))
    )
    (net (code "57") (name "/LCD_DATA6") (class "Default")
      (node (ref "J7") (pin "40") (pinfunction "LCD_DATA6_40") (pintype "passive"))
      (node (ref "R89") (pin "1") (pinfunction "1_1") (pintype "passive"))
      (node (ref "S2") (pin "13") (pinfunction "B4_13") (pintype "passive"))
    )
    (net (code "58") (name "/LCD_DATA7") (class "Default")
      (node (ref "J7") (pin "38") (pinfunction "LCD_DATA7_38") (pintype "passive"))
      (node (ref "R149") (pin "1") (pinfunction "1_1") (pintype "passive"))
      (node (ref "S2") (pin "12") (pinfunction "B5_12") (pintype "passive"))
    )
    (net (code "59") (name "/LCD_DATA8") (class "Default")
      (node (ref "J7") (pin "34") (pinfunction "LCD_DATA8_34") (pintype "passive"))
    )
    (net (code "60") (name "/LCD_DATA9") (class "Default")
      (node (ref "J7") (pin "32") (pinfunction "LCD_DATA9_32") (pintype "passive"))
    )
    (net (code "61") (name "/LCD_DATA10") (class "Default")
      (node (ref "J7") (pin "30") (pinfunction "LCD_DATA10_30") (pintype "passive"))
    )
    (net (code "62") (name "/LCD_DATA11") (class "Default")
      (node (ref "J7") (pin "28") (pinfunction "LCD_DATA11_28") (pintype "passive"))
      (node (ref "R148") (pin "1") (pinfunction "1_1") (pintype "passive"))
      (node (ref "S2") (pin "11") (pinfunction "B6_11") (pintype "passive"))
    )
    (net (code "63") (name "/LCD_DATA12") (class "Default")
      (node (ref "J7") (pin "26") (pinfunction "LCD_DATA12_26") (pintype "passive"))
    )
    (net (code "64") (name "/LCD_DATA13") (class "Default")
      (node (ref "J7") (pin "24") (pinfunction "LCD_DATA13_24") (pintype "passive"))
    )
    (net (code "65") (name "/LCD_DATA14") (class "Default")
      (node (ref "J7") (pin "22") (pinfunction "LCD_DATA14_22") (pintype "passive"))
    )
    (net (code "66") (name "/LCD_DATA15") (class "Default")
      (node (ref "J7") (pin "20") (pinfunction "LCD_DATA15_20") (pintype "passive"))
    )
    (net (code "67") (name "/LCD_DATA16") (class "Default")
      (node (ref "J7") (pin "16") (pinfunction "LCD_DATA16_16") (pintype "passive"))
      (node (ref "P3") (pin "8") (pinfunction "8_8") (pintype "passive"))
    )
    (net (code "68") (name "/LCD_DATA17") (class "Default")
      (node (ref "J7") (pin "14") (pinfunction "LCD_DATA17_14") (pintype "passive"))
      (node (ref "P3") (pin "7") (pinfunction "7_7") (pintype "passive"))
    )
    (net (code "69") (name "/LCD_DATA18") (class "Default")
      (node (ref "J7") (pin "12") (pinfunction "LCD_DATA18_12") (pintype "passive"))
      (node (ref "P3") (pin "6") (pinfunction "6_6") (pintype "passive"))
    )
    (net (code "70") (name "/LCD_DATA19") (class "Default")
      (node (ref "J7") (pin "10") (pinfunction "LCD_DATA19_10") (pintype "passive"))
      (node (ref "P3") (pin "5") (pinfunction "5_5") (pintype "passive"))
    )
    (net (code "71") (name "/LCD_DATA20") (class "Default")
      (node (ref "J7") (pin "8") (pinfunction "LCD_DATA20_8") (pintype "passive"))
      (node (ref "P3") (pin "4") (pinfunction "4_4") (pintype "passive"))
    )
    (net (code "72") (name "/LCD_DATA21") (class "Default")
      (node (ref "J7") (pin "6") (pinfunction "LCD_DATA21_6") (pintype "passive"))
      (node (ref "P3") (pin "3") (pinfunction "3_3") (pintype "passive"))
    )
    (net (code "73") (name "/LCD_DATA22") (class "Default")
      (node (ref "J7") (pin "4") (pinfunction "LCD_DATA22_4") (pintype "passive"))
      (node (ref "P3") (pin "2") (pinfunction "2_2") (pintype "passive"))
    )
    (net (code "74") (name "/LCD_DATA23") (class "Default")
      (node (ref "J7") (pin "2") (pinfunction "LCD_DATA23_2") (pintype "passive"))
      (node (ref "P3") (pin "1") (pinfunction "1_1") (pintype "passive"))
    )
    (net (code "75") (name "/LCD_DE") (class "Default")
      (node (ref "J7") (pin "5") (pinfunction "LCD_DE_5") (pintype "passive"))
    )
    (net (code "76") (name "/LCD_HSYNC") (class "Default")
      (node (ref "J7") (pin "1") (pinfunction "LCD_HSYNC_1") (pintype "passive"))
      (node (ref "R103") (pin "2") (pinfunction "2_2") (pintype "passive"))
    )
    (net (code "77") (name "/LCD_NPWREN") (class "Default")
      (node (ref "J6") (pin "60") (pinfunction "SNVS_TAMPER2_60") (pintype "passive"))
    )
    (net (code "78") (name "/LCD_PCLK") (class "Default")
      (node (ref "J7") (pin "9") (pinfunction "LCD_PCLK_9") (pintype "passive"))
    )
    (net (code "79") (name "/LCD_VSYNC") (class "Default")
      (node (ref "J7") (pin "3") (pinfunction "LCD_VSYNC_3") (pintype "passive"))
    )
    (net (code "80") (name "/MODE0") (class "Default")
      (node (ref "J6") (pin "68") (pinfunction "BOOT_MODE0_68") (pintype "passive"))
      (node (ref "R97") (pin "2") (pinfunction "2_2") (pintype "passive"))
      (node (ref "S2") (pin "10") (pinfunction "B7_10") (pintype "passive"))
    )
    (net (code "81") (name "/MODE1") (class "Default")
      (node (ref "J6") (pin "66") (pinfunction "BOOT_MODE1_66") (pintype "passive"))
      (node (ref "R96") (pin "2") (pinfunction "2_2") (pintype "passive"))
      (node (ref "S2") (pin "9") (pinfunction "B8_9") (pintype "passive"))
    )
    (net (code "82") (name "/MX6_POR_B") (class "Default")
      (node (ref "J6") (pin "74") (pinfunction "MX6_POR_B_74") (pintype "passive"))
      (node (ref "S3") (pin "1") (pinfunction "1_1") (pintype "passive"))
    )
    (net (code "83") (name "/NAND_ALE") (class "Default")
      (node (ref "J7") (pin "60") (pinfunction "NAND_ALE_60") (pintype "passive"))
    )
    (net (code "84") (name "/NAND_CLE") (class "Default")
      (node (ref "J7") (pin "62") (pinfunction "NAND_CLE_62") (pintype "passive"))
    )
    (net (code "85") (name "/NAND_DATA0") (class "Default")
      (node (ref "J7") (pin "45") (pinfunction "NAND_DATA0_45") (pintype "passive"))
    )
    (net (code "86") (name "/NAND_DATA1") (class "Default")
      (node (ref "J7") (pin "43") (pinfunction "NAND_DATA1_43") (pintype "passive"))
    )
    (net (code "87") (name "/NAND_DATA2") (class "Default")
      (node (ref "J7") (pin "41") (pinfunction "NAND_DATA2_41") (pintype "passive"))
    )
    (net (code "88") (name "/NAND_DATA3") (class "Default")
      (node (ref "J7") (pin "39") (pinfunction "NAND_DATA3_39") (pintype "passive"))
    )
    (net (code "89") (name "/NAND_DATA4") (class "Default")
      (node (ref "J7") (pin "37") (pinfunction "NAND_DATA4_37") (pintype "passive"))
    )
    (net (code "90") (name "/NAND_DATA5") (class "Default")
      (node (ref "J7") (pin "35") (pinfunction "NAND_DATA5_35") (pintype "passive"))
    )
    (net (code "91") (name "/NAND_DATA6") (class "Default")
      (node (ref "J7") (pin "33") (pinfunction "NAND_DATA6_33") (pintype "passive"))
    )
    (net (code "92") (name "/NAND_DATA7") (class "Default")
      (node (ref "J7") (pin "31") (pinfunction "NAND_DATA7_31") (pintype "passive"))
    )
    (net (code "93") (name "/NAND_DQS") (class "Default")
      (node (ref "J7") (pin "56") (pinfunction "NAND_DQS_56") (pintype "passive"))
    )
    (net (code "94") (name "/NAND_nCE0") (class "Default")
      (node (ref "J7") (pin "66") (pinfunction "NAND_nCE0_66") (pintype "passive"))
    )
    (net (code "95") (name "/NAND_nCE1") (class "Default")
      (node (ref "J7") (pin "64") (pinfunction "NAND_nCE1_64") (pintype "passive"))
    )
    (net (code "96") (name "/NAND_nRE") (class "Default")
      (node (ref "J7") (pin "49") (pinfunction "NAND_nRE_49") (pintype "passive"))
    )
    (net (code "97") (name "/NAND_nREADY") (class "Default")
      (node (ref "J7") (pin "68") (pinfunction "NAND_nREADY_68") (pintype "passive"))
    )
    (net (code "98") (name "/NAND_nWE") (class "Default")
      (node (ref "J7") (pin "47") (pinfunction "NAND_nWE_47") (pintype "passive"))
    )
    (net (code "99") (name "/NAND_nWP") (class "Default")
      (node (ref "J7") (pin "58") (pinfunction "NAND_nWP_58") (pintype "passive"))
    )
    (net (code "100") (name "/ONOFF") (class "Default")
      (node (ref "J6") (pin "70") (pinfunction "ONOFF_70") (pintype "passive"))
    )
    (net (code "101") (name "/PEN") (class "Default")
      (node (ref "Q12") (pin "1") (pinfunction "G_1") (pintype "passive"))
      (node (ref "Q13") (pin "1") (pinfunction "G_1") (pintype "passive"))
      (node (ref "Q14") (pin "3") (pinfunction "D_3") (pintype "passive"))
      (node (ref "R86") (pin "1") (pinfunction "1_1") (pintype "passive"))
    )
    (net (code "102") (name "/PG") (class "Default")
      (node (ref "J6") (pin "44") (pinfunction "SNVS_TAMPER9_44") (pintype "passive"))
    )
    (net (code "103") (name "/PMIC_ON_REQ") (class "Default")
      (node (ref "J6") (pin "76") (pinfunction "PMIC_ON_REQ_76") (pintype "passive"))
      (node (ref "R101") (pin "2") (pinfunction "2_2") (pintype "passive"))
    )
    (net (code "104") (name "/POR_B") (class "Default")
      (node (ref "J6") (pin "72") (pinfunction "POR_B_72") (pintype "passive"))
    )
    (net (code "105") (name "/SD1_CLK") (class "Default")
      (node (ref "R54") (pin "2") (pinfunction "2_2") (pintype "passive"))
    )
    (net (code "106") (name "/SD1_CMD") (class "Default")
      (node (ref "J7") (pin "76") (pinfunction "SD1_CMD_76") (pintype "passive"))
    )
    (net (code "107") (name "/SD1_DATA0") (class "Default")
      (node (ref "J7") (pin "70") (pinfunction "SD1_DATA0_70") (pintype "passive"))
    )
    (net (code "108") (name "/SD1_DATA1") (class "Default")
      (node (ref "J7") (pin "72") (pinfunction "SD1_DATA1_72") (pintype "passive"))
    )
    (net (code "109") (name "/SD1_DATA2") (class "Default")
      (node (ref "J7") (pin "80") (pinfunction "SD1_DATA2_80") (pintype "passive"))
    )
    (net (code "110") (name "/SD1_DATA3") (class "Default")
      (node (ref "J7") (pin "78") (pinfunction "SD1_DATA3_78") (pintype "passive"))
    )
    (net (code "111") (name "/SHUTDOWN") (class "Default")
      (node (ref "J6") (pin "50") (pinfunction "SNVS_TAMPER6_50") (pintype "passive"))
    )
    (net (code "112") (name "/TP_INT") (class "Default")
      (node (ref "J6") (pin "62") (pinfunction "SNVS_TAMPER1_62") (pintype "passive"))
    )
    (net (code "113") (name "/UART1_CTS") (class "Default")
      (node (ref "J6") (pin "27") (pinfunction "UART1_CTS_27") (pintype "passive"))
      (node (ref "P2") (pin "15") (pinfunction "15_15") (pintype "passive"))
    )
    (net (code "114") (name "/UART1_RTS") (class "Default")
      (node (ref "J6") (pin "29") (pinfunction "UART1_RTS_29") (pintype "passive"))
    )
    (net (code "115") (name "/UART1_RXD") (class "Default")
      (node (ref "J6") (pin "31") (pinfunction "UART1_RXD_31") (pintype "passive"))
    )
    (net (code "116") (name "/UART1_TXD") (class "Default")
      (node (ref "J6") (pin "33") (pinfunction "UART1_TXD_33") (pintype "passive"))
    )
    (net (code "117") (name "/UART2_CTS") (class "Default")
      (node (ref "J6") (pin "19") (pinfunction "UART2_CTS_19") (pintype "passive"))
      (node (ref "P2") (pin "12") (pinfunction "12_12") (pintype "passive"))
    )
    (net (code "118") (name "/UART2_RTS") (class "Default")
      (node (ref "J6") (pin "21") (pinfunction "UART2_RTS_21") (pintype "passive"))
      (node (ref "P2") (pin "11") (pinfunction "11_11") (pintype "passive"))
    )
    (net (code "119") (name "/UART2_RXD") (class "Default")
      (node (ref "J6") (pin "23") (pinfunction "UART2_RXD_23") (pintype "passive"))
      (node (ref "P2") (pin "14") (pinfunction "14_14") (pintype "passive"))
    )
    (net (code "120") (name "/UART2_TXD") (class "Default")
      (node (ref "J6") (pin "25") (pinfunction "UART2_TXD_25") (pintype "passive"))
      (node (ref "P2") (pin "13") (pinfunction "13_13") (pintype "passive"))
    )
    (net (code "121") (name "/UART3_CTS") (class "Default")
      (node (ref "J6") (pin "9") (pinfunction "UART3_CTS_9") (pintype "passive"))
      (node (ref "P2") (pin "5") (pinfunction "5_5") (pintype "passive"))
    )
    (net (code "122") (name "/UART3_RTS") (class "Default")
      (node (ref "J6") (pin "11") (pinfunction "UART3_RTS_11") (pintype "passive"))
      (node (ref "P2") (pin "8") (pinfunction "8_8") (pintype "passive"))
    )
    (net (code "123") (name "/UART3_RXD") (class "Default")
      (node (ref "J6") (pin "13") (pinfunction "UART3_RXD_13") (pintype "passive"))
      (node (ref "P2") (pin "7") (pinfunction "7_7") (pintype "passive"))
    )
    (net (code "124") (name "/UART3_TXD") (class "Default")
      (node (ref "J6") (pin "15") (pinfunction "UART3_TXD_15") (pintype "passive"))
      (node (ref "P2") (pin "9") (pinfunction "9_9") (pintype "passive"))
    )
    (net (code "125") (name "/UART4_RXD") (class "Default")
      (node (ref "J6") (pin "5") (pinfunction "UART4_RXD_5") (pintype "passive"))
      (node (ref "P2") (pin "3") (pinfunction "3_3") (pintype "passive"))
    )
    (net (code "126") (name "/UART4_TXD") (class "Default")
      (node (ref "J6") (pin "7") (pinfunction "UART4_TXD_7") (pintype "passive"))
      (node (ref "P2") (pin "6") (pinfunction "6_6") (pintype "passive"))
    )
    (net (code "127") (name "/UART5_RXD") (class "Default")
      (node (ref "J6") (pin "1") (pinfunction "UART5_RXD_1") (pintype "passive"))
      (node (ref "P2") (pin "1") (pinfunction "1_1") (pintype "passive"))
    )
    (net (code "128") (name "/UART5_TXD") (class "Default")
      (node (ref "J6") (pin "3") (pinfunction "UART5_TXD_3") (pintype "passive"))
      (node (ref "P2") (pin "2") (pinfunction "2_2") (pintype "passive"))
    )
    (net (code "129") (name "/USB_OTG1_ID") (class "Default")
      (node (ref "J6") (pin "36") (pinfunction "GPIO_0_36") (pintype "passive"))
    )
    (net (code "130") (name "/USB_OTG1_N") (class "Default")
      (node (ref "J6") (pin "69") (pinfunction "USB_OTG1_DN_69") (pintype "passive"))
    )
    (net (code "131") (name "/USB_OTG1_P") (class "Default")
      (node (ref "J6") (pin "67") (pinfunction "USB_OTG1_DP_67") (pintype "passive"))
    )
    (net (code "132") (name "/USB_OTG1_PWR") (class "Default")
      (node (ref "R103") (pin "1") (pinfunction "1_1") (pintype "passive"))
      (node (ref "R84") (pin "2") (pinfunction "2_2") (pintype "passive"))
    )
    (net (code "133") (name "/USB_OTG1_VBUS") (class "Default")
      (node (ref "J6") (pin "71") (pinfunction "USB_OTG1_VBUS_71") (pintype "passive"))
    )
    (net (code "134") (name "/USB_OTG2_ID") (class "Default")
      (node (ref "J6") (pin "26") (pinfunction "GPIO_5_26") (pintype "passive"))
    )
    (net (code "135") (name "/USB_OTG2_N") (class "Default")
      (node (ref "J6") (pin "57") (pinfunction "USB_OTG2_DN_57") (pintype "passive"))
    )
    (net (code "136") (name "/USB_OTG2_P") (class "Default")
      (node (ref "J6") (pin "59") (pinfunction "USB_OTG2_DP_59") (pintype "passive"))
    )
    (net (code "137") (name "/USB_OTG2_VBUS") (class "Default")
      (node (ref "J6") (pin "61") (pinfunction "USB_OTG2_VBUS_61") (pintype "passive"))
    )
    (net (code "139") (name "/VIN") (class "Default")
      (node (ref "P4") (pin "2") (pinfunction "2_2") (pintype "passive"))
      (node (ref "P4") (pin "5") (pinfunction "5_5") (pintype "passive"))
      (node (ref "P7") (pin "1") (pinfunction "1_1") (pintype "passive"))
    )
    (net (code "140") (name "GEN_3V3") (class "Default")
      (node (ref "C28") (pin "2") (pinfunction "2_2") (pintype "passive"))
      (node (ref "J7") (pin "79") (pinfunction "NVCC_CSI_IN_79") (pintype "passive"))
      (node (ref "P3") (pin "21") (pinfunction "21_21") (pintype "passive"))
      (node (ref "P3") (pin "22") (pinfunction "22_22") (pintype "passive"))
      (node (ref "P5") (pin "1") (pinfunction "1_1") (pintype "passive"))
      (node (ref "Q13") (pin "3") (pinfunction "D_3") (pintype "passive"))
      (node (ref "R100") (pin "1") (pinfunction "1_1") (pintype "passive"))
      (node (ref "R143") (pin "1") (pinfunction "1_1") (pintype "passive"))
      (node (ref "R144") (pin "1") (pinfunction "1_1") (pintype "passive"))
      (node (ref "R145") (pin "1") (pinfunction "1_1") (pintype "passive"))
      (node (ref "R146") (pin "1") (pinfunction "1_1") (pintype "passive"))
      (node (ref "R147") (pin "1") (pinfunction "1_1") (pintype "passive"))
      (node (ref "R55") (pin "2") (pinfunction "2_2") (pintype "passive"))
      (node (ref "R56") (pin "2") (pinfunction "2_2") (pintype "passive"))
      (node (ref "R60") (pin "2") (pinfunction "2_2") (pintype "passive"))
      (node (ref "R61") (pin "2") (pinfunction "2_2") (pintype "passive"))
      (node (ref "R62") (pin "2") (pinfunction "2_2") (pintype "passive"))
      (node (ref "R63") (pin "2") (pinfunction "2_2") (pintype "passive"))
      (node (ref "R87") (pin "2") (pinfunction "2_2") (pintype "passive"))
      (node (ref "R98") (pin "1") (pinfunction "1_1") (pintype "passive"))
      (node (ref "R99") (pin "1") (pinfunction "1_1") (pintype "passive"))
    )
    (net (code "141") (name "GEN_5V") (class "Default")
      (node (ref "Q12") (pin "3") (pinfunction "D_3") (pintype "passive"))
      (node (ref "R85") (pin "1") (pinfunction "1_1") (pintype "passive"))
    )
    (net (code "142") (name "GND") (class "Default")
      (node (ref "C28") (pin "1") (pinfunction "1_1") (pintype "passive"))
      (node (ref "C29") (pin "2") (pinfunction "2_2") (pintype "passive"))
      (node (ref "C47") (pin "2") (pinfunction "2_2") (pintype "passive"))
      (node (ref "C49") (pin "1") (pinfunction "1_1") (pintype "passive"))
      (node (ref "C50") (pin "2") (pinfunction "2_2") (pintype "passive"))
      (node (ref "C51") (pin "2") (pinfunction "2_2") (pintype "passive"))
      (node (ref "C59") (pin "1") (pinfunction "1_1") (pintype "passive"))
      (node (ref "D14") (pin "2") (pinfunction "K_2") (pintype "passive"))
      (node (ref "D15") (pin "1") (pinfunction "A_1") (pintype "passive"))
      (node (ref "D16") (pin "1") (pinfunction "A_1") (pintype "passive"))
      (node (ref "D17") (pin "2") (pinfunction "K_2") (pintype "passive"))
      (node (ref "H10") (pin "1") (pinfunction "1_1") (pintype "passive"))
      (node (ref "H11") (pin "1") (pinfunction "1_1") (pintype "passive"))
      (node (ref "J6") (pin "17") (pinfunction "GND_17") (pintype "passive"))
      (node (ref "J6") (pin "2") (pinfunction "GND_2") (pintype "passive"))
      (node (ref "J6") (pin "24") (pinfunction "GND_24") (pintype "passive"))
      (node (ref "J6") (pin "35") (pinfunction "GND_35") (pintype "passive"))
      (node (ref "J6") (pin "42") (pinfunction "GND_42") (pintype "passive"))
      (node (ref "J6") (pin "49") (pinfunction "GND_49") (pintype "passive"))
      (node (ref "J6") (pin "55") (pinfunction "GND_55") (pintype "passive"))
      (node (ref "J6") (pin "58") (pinfunction "GND_58") (pintype "passive"))
      (node (ref "J6") (pin "63") (pinfunction "GND_63") (pintype "passive"))
      (node (ref "J6") (pin "75") (pinfunction "GND_75") (pintype "passive"))
      (node (ref "J6") (pin "80") (pinfunction "GND_80") (pintype "passive"))
      (node (ref "J7") (pin "18") (pinfunction "GND_18") (pintype "passive"))
      (node (ref "J7") (pin "29") (pinfunction "GND_29") (pintype "passive"))
      (node (ref "J7") (pin "36") (pinfunction "GND_36") (pintype "passive"))
      (node (ref "J7") (pin "54") (pinfunction "GND_54") (pintype "passive"))
      (node (ref "J7") (pin "59") (pinfunction "GND_59") (pintype "passive"))
      (node (ref "J7") (pin "7") (pinfunction "GND_7") (pintype "passive"))
      (node (ref "J7") (pin "77") (pinfunction "GND_77") (pintype "passive"))
      (node (ref "P2") (pin "10") (pinfunction "10_10") (pintype "passive"))
      (node (ref "P2") (pin "16") (pinfunction "16_16") (pintype "passive"))
      (node (ref "P2") (pin "4") (pinfunction "4_4") (pintype "passive"))
      (node (ref "P3") (pin "23") (pinfunction "23_23") (pintype "passive"))
      (node (ref "P3") (pin "24") (pinfunction "24_24") (pintype "passive"))
      (node (ref "P5") (pin "2") (pinfunction "2_2") (pintype "passive"))
      (node (ref "P7") (pin "2") (pinfunction "2_2") (pintype "passive"))
      (node (ref "P7") (pin "3") (pinfunction "3_3") (pintype "passive"))
      (node (ref "Q14") (pin "2") (pinfunction "S_2") (pintype "passive"))
      (node (ref "R102") (pin "1") (pinfunction "1_1") (pintype "passive"))
      (node (ref "R133") (pin "2") (pinfunction "2_2") (pintype "passive"))
      (node (ref "R142") (pin "2") (pinfunction "2_2") (pintype "passive"))
      (node (ref "R148") (pin "2") (pinfunction "2_2") (pintype "passive"))
      (node (ref "R149") (pin "2") (pinfunction "2_2") (pintype "passive"))
      (node (ref "R88") (pin "2") (pinfunction "2_2") (pintype "passive"))
      (node (ref "R89") (pin "2") (pinfunction "2_2") (pintype "passive"))
      (node (ref "R92") (pin "2") (pinfunction "2_2") (pintype "passive"))
      (node (ref "R93") (pin "2") (pinfunction "2_2") (pintype "passive"))
      (node (ref "R96") (pin "1") (pinfunction "1_1") (pintype "passive"))
      (node (ref "R97") (pin "1") (pinfunction "1_1") (pintype "passive"))
      (node (ref "S3") (pin "2") (pinfunction "2_2") (pintype "passive"))
      (node (ref "S3") (pin "3") (pinfunction "3_3") (pintype "passive"))
      (node (ref "S3") (pin "4") (pinfunction "4_4") (pintype "passive"))
      (node (ref "U10") (pin "8") (pinfunction "VSS_8") (pintype "passive"))
      (node (ref "U12") (pin "2") (pinfunction "K_2") (pintype "passive"))
      (node (ref "U7") (pin "1") (pinfunction "GND_1") (pintype "passive"))
    )
    (net (code "143") (name "Net-(C60-Pad2)") (class "Default")
      (node (ref "C60") (pin "2") (pinfunction "2_2") (pintype "passive"))
      (node (ref "C61") (pin "2") (pinfunction "2_2") (pintype "passive"))
      (node (ref "R129") (pin "2") (pinfunction "2_2") (pintype "passive"))
      (node (ref "R131") (pin "2") (pinfunction "2_2") (pintype "passive"))
    )
    (net (code "144") (name "Net-(D4-A)") (class "Default")
      (node (ref "D4") (pin "1") (pinfunction "A_1") (pintype "passive"))
      (node (ref "R60") (pin "1") (pinfunction "1_1") (pintype "passive"))
    )
    (net (code "145") (name "Net-(D5-A)") (class "Default")
      (node (ref "D5") (pin "1") (pinfunction "A_1") (pintype "passive"))
      (node (ref "R61") (pin "1") (pinfunction "1_1") (pintype "passive"))
    )
    (net (code "146") (name "Net-(D6-A)") (class "Default")
      (node (ref "D6") (pin "1") (pinfunction "A_1") (pintype "passive"))
      (node (ref "R62") (pin "1") (pinfunction "1_1") (pintype "passive"))
    )
    (net (code "147") (name "Net-(D7-A)") (class "Default")
      (node (ref "D7") (pin "1") (pinfunction "A_1") (pintype "passive"))
      (node (ref "R118") (pin "1") (pinfunction "1_1") (pintype "passive"))
      (node (ref "U11") (pin "3") (pinfunction "3_3") (pintype "passive"))
    )
    (net (code "148") (name "Net-(D7-K)") (class "Default")
      (node (ref "D7") (pin "2") (pinfunction "K_2") (pintype "passive"))
      (node (ref "R133") (pin "1") (pinfunction "1_1") (pintype "passive"))
      (node (ref "R135") (pin "2") (pinfunction "2_2") (pintype "passive"))
      (node (ref "U10") (pin "12") (pinfunction "RST_12") (pintype "passive"))
    )
    (net (code "149") (name "Net-(D8-A)") (class "Default")
      (node (ref "D8") (pin "1") (pinfunction "A_1") (pintype "passive"))
      (node (ref "R63") (pin "1") (pinfunction "1_1") (pintype "passive"))
    )
    (net (code "150") (name "Net-(D14-A)") (class "Default")
      (node (ref "D14") (pin "1") (pinfunction "A_1") (pintype "passive"))
      (node (ref "R134") (pin "1") (pinfunction "1_1") (pintype "passive"))
    )
    (net (code "151") (name "Net-(D15-K)") (class "Default")
      (node (ref "D15") (pin "2") (pinfunction "K_2") (pintype "passive"))
      (node (ref "R137") (pin "2") (pinfunction "2_2") (pintype "passive"))
      (node (ref "R138") (pin "2") (pinfunction "2_2") (pintype "passive"))
      (node (ref "R139") (pin "2") (pinfunction "2_2") (pintype "passive"))
      (node (ref "R141") (pin "2") (pinfunction "2_2") (pintype "passive"))
    )
    (net (code "152") (name "Net-(D16-K)") (class "Default")
      (node (ref "D16") (pin "2") (pinfunction "K_2") (pintype "passive"))
      (node (ref "F1") (pin "2") (pinfunction "2_2") (pintype "passive"))
      (node (ref "Q16") (pin "2") (pinfunction "S_2") (pintype "passive"))
      (node (ref "Q17") (pin "2") (pinfunction "E_2") (pintype "passive"))
      (node (ref "R137") (pin "1") (pinfunction "1_1") (pintype "passive"))
      (node (ref "R138") (pin "1") (pinfunction "1_1") (pintype "passive"))
      (node (ref "R139") (pin "1") (pinfunction "1_1") (pintype "passive"))
    )
    (net (code "153") (name "Net-(D17-A)") (class "Default")
      (node (ref "D17") (pin "1") (pinfunction "A_1") (pintype "passive"))
      (node (ref "R140") (pin "1") (pinfunction "1_1") (pintype "passive"))
    )
    (net (code "154") (name "Net-(F1-Pad1)") (class "Default")
      (node (ref "F1") (pin "1") (pinfunction "1_1") (pintype "passive"))
      (node (ref "P4") (pin "3") (pinfunction "3_3") (pintype "passive"))
      (node (ref "P4") (pin "6") (pinfunction "6_6") (pintype "passive"))
    )
    (net (code "155") (name "Net-(J7-SD1_CLK)") (class "Default")
      (node (ref "J7") (pin "74") (pinfunction "SD1_CLK_74") (pintype "passive"))
      (node (ref "R54") (pin "1") (pinfunction "1_1") (pintype "passive"))
    )
    (net (code "156") (name "Net-(Q14-G)") (class "Default")
      (node (ref "Q14") (pin "1") (pinfunction "G_1") (pintype "passive"))
      (node (ref "R101") (pin "1") (pinfunction "1_1") (pintype "passive"))
      (node (ref "R102") (pin "2") (pinfunction "2_2") (pintype "passive"))
    )
    (net (code "157") (name "Net-(Q15-G)") (class "Default")
      (node (ref "Q15") (pin "1") (pinfunction "G_1") (pintype "passive"))
      (node (ref "R112") (pin "1") (pinfunction "1_1") (pintype "passive"))
      (node (ref "R115") (pin "2") (pinfunction "2_2") (pintype "passive"))
      (node (ref "R119") (pin "1") (pinfunction "1_1") (pintype "passive"))
      (node (ref "R121") (pin "1") (pinfunction "1_1") (pintype "passive"))
      (node (ref "R125") (pin "2") (pinfunction "2_2") (pintype "passive"))
      (node (ref "R126") (pin "1") (pinfunction "1_1") (pintype "passive"))
      (node (ref "R128") (pin "1") (pinfunction "1_1") (pintype "passive"))
      (node (ref "U11") (pin "1") (pinfunction "1_1") (pintype "passive"))
    )
    (net (code "158") (name "Net-(Q16-G)") (class "Default")
      (node (ref "Q16") (pin "1") (pinfunction "G_1") (pintype "passive"))
      (node (ref "Q17") (pin "3") (pinfunction "C_3") (pintype "passive"))
      (node (ref "R142") (pin "1") (pinfunction "1_1") (pintype "passive"))
    )
    (net (code "159") (name "Net-(Q17-B)") (class "Default")
      (node (ref "Q17") (pin "1") (pinfunction "B_1") (pintype "passive"))
      (node (ref "R141") (pin "1") (pinfunction "1_1") (pintype "passive"))
    )
    (net (code "160") (name "Net-(R113-Pad1)") (class "Default")
      (node (ref "R113") (pin "1") (pinfunction "1_1") (pintype "passive"))
      (node (ref "R114") (pin "2") (pinfunction "2_2") (pintype "passive"))
      (node (ref "R115") (pin "1") (pinfunction "1_1") (pintype "passive"))
      (node (ref "R122") (pin "2") (pinfunction "2_2") (pintype "passive"))
      (node (ref "R124") (pin "1") (pinfunction "1_1") (pintype "passive"))
      (node (ref "R130") (pin "1") (pinfunction "1_1") (pintype "passive"))
      (node (ref "U11") (pin "2") (pinfunction "2_2") (pintype "passive"))
    )
    (net (code "161") (name "Net-(S2-A1)") (class "Default")
      (node (ref "R145") (pin "2") (pinfunction "2_2") (pintype "passive"))
      (node (ref "S2") (pin "1") (pinfunction "A1_1") (pintype "passive"))
    )
    (net (code "162") (name "Net-(S2-A2)") (class "Default")
      (node (ref "R144") (pin "2") (pinfunction "2_2") (pintype "passive"))
      (node (ref "S2") (pin "2") (pinfunction "A2_2") (pintype "passive"))
    )
    (net (code "163") (name "Net-(S2-A3)") (class "Default")
      (node (ref "R146") (pin "2") (pinfunction "2_2") (pintype "passive"))
      (node (ref "S2") (pin "3") (pinfunction "A3_3") (pintype "passive"))
    )
    (net (code "164") (name "Net-(S2-A4)") (class "Default")
      (node (ref "R147") (pin "2") (pinfunction "2_2") (pintype "passive"))
      (node (ref "S2") (pin "4") (pinfunction "A4_4") (pintype "passive"))
    )
    (net (code "165") (name "Net-(S2-A5)") (class "Default")
      (node (ref "R99") (pin "2") (pinfunction "2_2") (pintype "passive"))
      (node (ref "S2") (pin "5") (pinfunction "A5_5") (pintype "passive"))
    )
    (net (code "166") (name "Net-(S2-A6)") (class "Default")
      (node (ref "R143") (pin "2") (pinfunction "2_2") (pintype "passive"))
      (node (ref "S2") (pin "6") (pinfunction "A6_6") (pintype "passive"))
    )
    (net (code "167") (name "Net-(S2-A7)") (class "Default")
      (node (ref "R98") (pin "2") (pinfunction "2_2") (pintype "passive"))
      (node (ref "S2") (pin "7") (pinfunction "A7_7") (pintype "passive"))
    )
    (net (code "168") (name "Net-(S2-A8)") (class "Default")
      (node (ref "R100") (pin "2") (pinfunction "2_2") (pintype "passive"))
      (node (ref "S2") (pin "8") (pinfunction "A8_8") (pintype "passive"))
    )
    (net (code "169") (name "Net-(U10-F0)") (class "Default")
      (node (ref "C60") (pin "1") (pinfunction "1_1") (pintype "passive"))
      (node (ref "C61") (pin "1") (pinfunction "1_1") (pintype "passive"))
      (node (ref "U10") (pin "9") (pinfunction "F0_9") (pintype "passive"))
    )
    (net (code "170") (name "Net-(U10-F1)") (class "Default")
      (node (ref "R129") (pin "1") (pinfunction "1_1") (pintype "passive"))
      (node (ref "U10") (pin "11") (pinfunction "F1_11") (pintype "passive"))
    )
    (net (code "171") (name "Net-(U10-Q4)") (class "Default")
      (node (ref "R130") (pin "2") (pinfunction "2_2") (pintype "passive"))
      (node (ref "R134") (pin "2") (pinfunction "2_2") (pintype "passive"))
      (node (ref "U10") (pin "7") (pinfunction "Q4_7") (pintype "passive"))
    )
    (net (code "172") (name "Net-(U10-Q5)") (class "Default")
      (node (ref "R126") (pin "2") (pinfunction "2_2") (pintype "passive"))
      (node (ref "U10") (pin "5") (pinfunction "Q5_5") (pintype "passive"))
    )
    (net (code "173") (name "Net-(U10-Q6)") (class "Default")
      (node (ref "R124") (pin "2") (pinfunction "2_2") (pintype "passive"))
      (node (ref "U10") (pin "4") (pinfunction "Q6_4") (pintype "passive"))
    )
    (net (code "174") (name "Net-(U10-Q7)") (class "Default")
      (node (ref "R128") (pin "2") (pinfunction "2_2") (pintype "passive"))
      (node (ref "U10") (pin "6") (pinfunction "Q7_6") (pintype "passive"))
    )
    (net (code "175") (name "Net-(U10-Q8)") (class "Default")
      (node (ref "R122") (pin "1") (pinfunction "1_1") (pintype "passive"))
      (node (ref "U10") (pin "14") (pinfunction "Q8_14") (pintype "passive"))
    )
    (net (code "176") (name "Net-(U10-Q9)") (class "Default")
      (node (ref "R125") (pin "1") (pinfunction "1_1") (pintype "passive"))
      (node (ref "U10") (pin "13") (pinfunction "Q9_13") (pintype "passive"))
    )
    (net (code "177") (name "Net-(U10-Q10)") (class "Default")
      (node (ref "R114") (pin "1") (pinfunction "1_1") (pintype "passive"))
      (node (ref "U10") (pin "15") (pinfunction "Q10_15") (pintype "passive"))
    )
    (net (code "178") (name "Net-(U10-Q12)") (class "Default")
      (node (ref "R112") (pin "2") (pinfunction "2_2") (pintype "passive"))
      (node (ref "U10") (pin "1") (pinfunction "Q12_1") (pintype "passive"))
    )
    (net (code "179") (name "Net-(U10-Q13)") (class "Default")
      (node (ref "R113") (pin "2") (pinfunction "2_2") (pintype "passive"))
      (node (ref "U10") (pin "2") (pinfunction "Q13_2") (pintype "passive"))
    )
    (net (code "180") (name "Net-(U10-Q14)") (class "Default")
      (node (ref "R121") (pin "2") (pinfunction "2_2") (pintype "passive"))
      (node (ref "U10") (pin "3") (pinfunction "Q14_3") (pintype "passive"))
    )
    (net (code "181") (name "Net-(U10-~{F0})") (class "Default")
      (node (ref "R131") (pin "1") (pinfunction "1_1") (pintype "passive"))
      (node (ref "U10") (pin "10") (pinfunction "~{F0}_10") (pintype "passive"))
    )
    (net (code "182") (name "Net-(U12-A)") (class "Default")
      (node (ref "R136") (pin "2") (pinfunction "2_2") (pintype "passive"))
      (node (ref "U12") (pin "1") (pinfunction "A_1") (pintype "passive"))
    )
    (net (code "183") (name "Net-(U12-E)") (class "Default")
      (node (ref "R135") (pin "1") (pinfunction "1_1") (pintype "passive"))
      (node (ref "U12") (pin "3") (pinfunction "E_3") (pintype "passive"))
    )
    (net (code "184") (name "VDD_3V3") (class "Default")
      (node (ref "C50") (pin "1") (pinfunction "1_1") (pintype "passive"))
      (node (ref "C51") (pin "1") (pinfunction "1_1") (pintype "passive"))
      (node (ref "Q13") (pin "2") (pinfunction "S_2") (pintype "passive"))
      (node (ref "R87") (pin "1") (pinfunction "1_1") (pintype "passive"))
      (node (ref "U7") (pin "2") (pinfunction "2_2") (pintype "passive"))
      (node (ref "U7") (pin "4") (pinfunction "Vout_4") (pintype "passive"))
    )
    (net (code "185") (name "VDD_5V") (class "Default")
      (node (ref "C29") (pin "1") (pinfunction "1_1") (pintype "passive"))
      (node (ref "C47") (pin "1") (pinfunction "1_1") (pintype "passive"))
      (node (ref "C49") (pin "2") (pinfunction "2_2") (pintype "passive"))
      (node (ref "J6") (pin "77") (pinfunction "VSYS_77") (pintype "passive"))
      (node (ref "J6") (pin "79") (pinfunction "VSYS_79") (pintype "passive"))
      (node (ref "Q12") (pin "2") (pinfunction "S_2") (pintype "passive"))
      (node (ref "Q15") (pin "3") (pinfunction "D_3") (pintype "passive"))
      (node (ref "R110") (pin "1") (pinfunction "1_1") (pintype "passive"))
      (node (ref "R85") (pin "2") (pinfunction "2_2") (pintype "passive"))
      (node (ref "R86") (pin "2") (pinfunction "2_2") (pintype "passive"))
      (node (ref "U7") (pin "3") (pinfunction "Vin_3") (pintype "passive"))
    )
    (net (code "186") (name "VRTC") (class "Default")
      (node (ref "J6") (pin "73") (pinfunction "VDD_COIN_3V_73") (pintype "passive"))
    )
    (net (code "187") (name "unconnected-(J6-CLK1_N-Pad51)") (class "Default")
      (node (ref "J6") (pin "51") (pinfunction "CLK1_N_51") (pintype "passive"))
    )
    (net (code "188") (name "unconnected-(J6-CLK1_P-Pad53)") (class "Default")
      (node (ref "J6") (pin "53") (pinfunction "CLK1_P_53") (pintype "passive"))
    )
    (net (code "189") (name "unconnected-(J6-GPIO_9-Pad38)") (class "Default")
      (node (ref "J6") (pin "38") (pinfunction "GPIO_9_38") (pintype "passive"))
    )
    (net (code "190") (name "unconnected-(J6-PMIC_STBY_REQ-Pad78)") (class "Default")
      (node (ref "J6") (pin "78") (pinfunction "PMIC_STBY_REQ_78") (pintype "passive"))
    )
    (net (code "191") (name "unconnected-(J6-nUSB_OTG1_CHD-Pad65)") (class "Default")
      (node (ref "J6") (pin "65") (pinfunction "nUSB_OTG1_CHD_65") (pintype "passive"))
    )
    (net (code "192") (name "unconnected-(J7-LCD_RST-Pad11)") (class "Default")
      (node (ref "J7") (pin "11") (pinfunction "LCD_RST_11") (pintype "passive"))
    )
    (net (code "193") (name "unconnected-(P4-Pad1)") (class "Default")
      (node (ref "P4") (pin "1") (pinfunction "1_1") (pintype "passive"))
    )
    (net (code "194") (name "unconnected-(P4-Pad4)") (class "Default")
      (node (ref "P4") (pin "4") (pinfunction "4_4") (pintype "passive"))
    )
  )
)
